# PCB_RFID-Project.net
KiCad netlist of a schematic drawn in Altium Designer
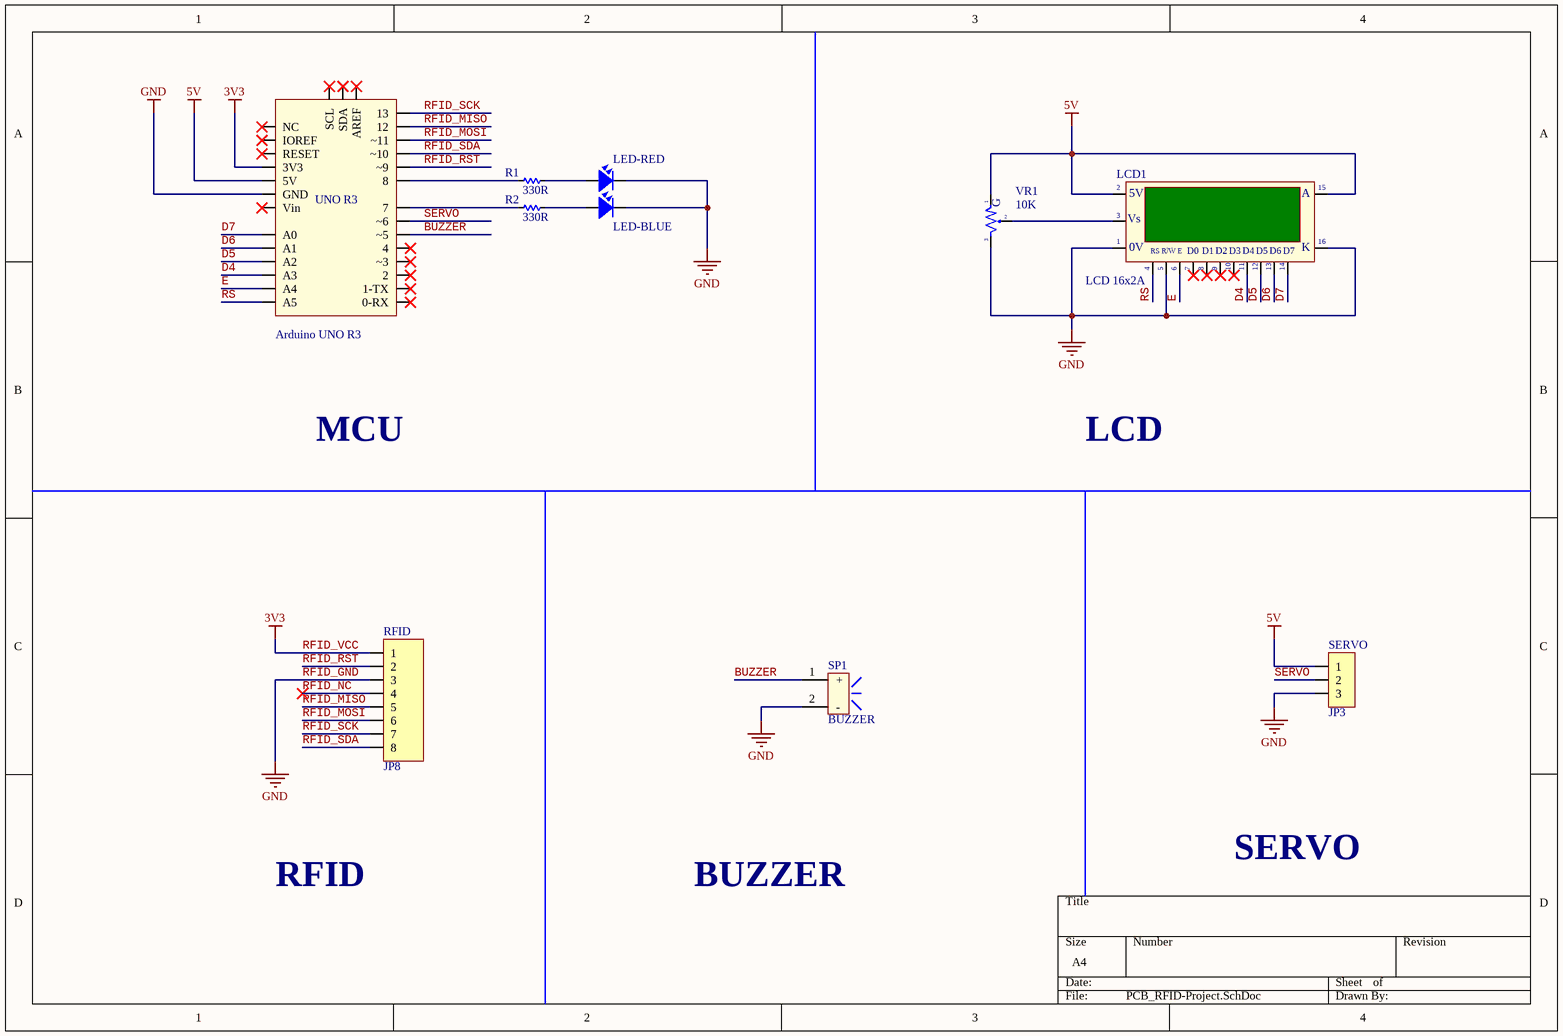
[diagram p0: PCB_RFID-Project.SchDoc]

(export (version "E")
  (design (tool "Eeschema 10.0.6"))
  (components
    (comp (ref "Arduino UNO R3")
      (value "Arduino Uno R3")
      (footprint "Arduino UNO R3")
      (description "Arduino UNO R3")
      (libsource (lib "LIBRARY_MuaLinhKien") (part "Arduino Uno R3"))
    )
    (comp (ref "LCD1")
      (value "LCD 16x2A")
      (footprint "LCD16X2")
      (description "LCD dipslay 16 char, 2 line")
      (libsource (lib "MinhHa_Integrated_Library") (part "LCD16x2A"))
    )
    (comp (ref "LED-BLUE")
      (value "LED")
      (footprint "LED-5MM-BLUE")
      (description "LED Single colour Green and Red")
      (libsource (lib "LIBRARY_MuaLinhKien") (part "LED"))
    )
    (comp (ref "LED-RED")
      (value "LED")
      (footprint "LED-5MM-RED")
      (description "LED Single colour Green and Red")
      (libsource (lib "LIBRARY_MuaLinhKien") (part "LED"))
    )
    (comp (ref "R1")
      (value "330R")
      (footprint "RES-1/4W")
      (description "Res")
      (fields
        (field (name "MANUFACTURER") "Generic Components")
        (field (name "PUBLISHER") "Altium Hobart Technology Centre")
      )
      (libsource (lib "LIBRARY_MuaLinhKien") (part "Res"))
    )
    (comp (ref "R2")
      (value "330R")
      (footprint "RES-1/4W")
      (description "Res")
      (fields
        (field (name "MANUFACTURER") "Generic Components")
        (field (name "PUBLISHER") "Altium Hobart Technology Centre")
      )
      (libsource (lib "LIBRARY_MuaLinhKien") (part "Res"))
    )
    (comp (ref "RFID")
      (value "JP8")
      (footprint "JP8-D1T")
      (description "WR-PHD 2.54 mm Angled Socket Header")
      (fields
        (field (name "MANUFACTURER") "Würth Elektronik eiSos GmbH")
        (field (name "PARTNO") "613008143121")
        (field (name "CREATED BY") "Karrer Zheng")
      )
      (libsource (lib "LIBRARY_MuaLinhKien") (part "JP8"))
    )
    (comp (ref "SERVO")
      (value "JP3")
      (footprint "JP3-D1T")
      (description "WR-PHD 2.54 mm Angled Socket Header")
      (fields
        (field (name "MANUFACTURER") "Würth Elektronik eiSos GmbH")
        (field (name "PARTNO") "613003143121")
        (field (name "CREATED BY") "Karrer Zheng")
      )
      (libsource (lib "LIBRARY_MuaLinhKien") (part "JP3"))
    )
    (comp (ref "SP1")
      (value "BUZZER")
      (footprint "Buzzer 5V 9x1.2mm")
      (description "Buzzer through hole (3V3/5V/12V)")
      (libsource (lib "Duc") (part "Speaker"))
    )
    (comp (ref "VR1")
      (value "10K")
      (footprint "VR-S2")
      (description "Var Resistor")
      (libsource (lib "LIBRARY_MuaLinhKien") (part "VR-S"))
    )
  )
  (nets
    (net (code "1") (name "/BUZZER") (class "Default")
      (node (ref "Arduino UNO R3") (pin "~5") (pinfunction "~5_~5") (pintype "passive"))
      (node (ref "SP1") (pin "1") (pinfunction "+_1") (pintype "passive"))
    )
    (net (code "2") (name "/D4") (class "Default")
      (node (ref "Arduino UNO R3") (pin "A3") (pinfunction "A3_A3") (pintype "passive"))
      (node (ref "LCD1") (pin "11") (pinfunction "D4_11") (pintype "passive"))
    )
    (net (code "3") (name "/D5") (class "Default")
      (node (ref "Arduino UNO R3") (pin "A2") (pinfunction "A2_A2") (pintype "passive"))
      (node (ref "LCD1") (pin "12") (pinfunction "D5_12") (pintype "passive"))
    )
    (net (code "4") (name "/D6") (class "Default")
      (node (ref "Arduino UNO R3") (pin "A1") (pinfunction "A1_A1") (pintype "passive"))
      (node (ref "LCD1") (pin "13") (pinfunction "D6_13") (pintype "passive"))
    )
    (net (code "5") (name "/D7") (class "Default")
      (node (ref "Arduino UNO R3") (pin "A0") (pinfunction "A0_A0") (pintype "passive"))
      (node (ref "LCD1") (pin "14") (pinfunction "D7_14") (pintype "passive"))
    )
    (net (code "6") (name "/E") (class "Default")
      (node (ref "Arduino UNO R3") (pin "A4") (pinfunction "A4_A4") (pintype "passive"))
      (node (ref "LCD1") (pin "6") (pinfunction "~{EN}_6") (pintype "passive"))
    )
    (net (code "7") (name "/RFID_MISO") (class "Default")
      (node (ref "Arduino UNO R3") (pin "12") (pinfunction "12_12") (pintype "passive"))
      (node (ref "RFID") (pin "5") (pinfunction "5_5") (pintype "passive"))
    )
    (net (code "8") (name "/RFID_MOSI") (class "Default")
      (node (ref "Arduino UNO R3") (pin "~11") (pinfunction "~11_~11") (pintype "passive"))
      (node (ref "RFID") (pin "6") (pinfunction "6_6") (pintype "passive"))
    )
    (net (code "9") (name "/RFID_NC") (class "Default")
      (node (ref "RFID") (pin "4") (pinfunction "4_4") (pintype "passive+no_connect"))
    )
    (net (code "10") (name "/RFID_RST") (class "Default")
      (node (ref "Arduino UNO R3") (pin "~9") (pinfunction "~9_~9") (pintype "passive"))
      (node (ref "RFID") (pin "2") (pinfunction "2_2") (pintype "passive"))
    )
    (net (code "11") (name "/RFID_SCK") (class "Default")
      (node (ref "Arduino UNO R3") (pin "13") (pinfunction "13_13") (pintype "passive"))
      (node (ref "RFID") (pin "7") (pinfunction "7_7") (pintype "passive"))
    )
    (net (code "12") (name "/RFID_SDA") (class "Default")
      (node (ref "Arduino UNO R3") (pin "~10") (pinfunction "~10_~10") (pintype "passive"))
      (node (ref "RFID") (pin "8") (pinfunction "8_8") (pintype "passive"))
    )
    (net (code "13") (name "/RS") (class "Default")
      (node (ref "Arduino UNO R3") (pin "A5") (pinfunction "A5_A5") (pintype "passive"))
      (node (ref "LCD1") (pin "4") (pinfunction "RS_4") (pintype "passive"))
    )
    (net (code "14") (name "/SERVO") (class "Default")
      (node (ref "Arduino UNO R3") (pin "~6") (pinfunction "~6_~6") (pintype "passive"))
      (node (ref "SERVO") (pin "2") (pinfunction "2_2") (pintype "passive"))
    )
    (net (code "15") (name "3V3") (class "Default")
      (node (ref "Arduino UNO R3") (pin "3V3") (pinfunction "3V3_3V3") (pintype "passive"))
      (node (ref "RFID") (pin "1") (pinfunction "1_1") (pintype "passive"))
    )
    (net (code "16") (name "5V") (class "Default")
      (node (ref "Arduino UNO R3") (pin "5V") (pinfunction "5V_5V") (pintype "passive"))
      (node (ref "LCD1") (pin "15") (pinfunction "A_15") (pintype "passive"))
      (node (ref "LCD1") (pin "2") (pinfunction "VDD_2") (pintype "passive"))
      (node (ref "SERVO") (pin "1") (pinfunction "1_1") (pintype "passive"))
      (node (ref "VR1") (pin "1") (pinfunction "1_1") (pintype "passive"))
    )
    (net (code "17") (name "GND") (class "Default")
      (node (ref "Arduino UNO R3") (pin "GND") (pinfunction "GND_GND") (pintype "passive"))
      (node (ref "LCD1") (pin "1") (pinfunction "GND_1") (pintype "passive"))
      (node (ref "LCD1") (pin "16") (pinfunction "K_16") (pintype "passive"))
      (node (ref "LCD1") (pin "5") (pinfunction "R/~{W}_5") (pintype "passive"))
      (node (ref "LED-BLUE") (pin "2") (pinfunction "2_2") (pintype "passive"))
      (node (ref "LED-RED") (pin "2") (pinfunction "2_2") (pintype "passive"))
      (node (ref "RFID") (pin "3") (pinfunction "3_3") (pintype "passive"))
      (node (ref "SERVO") (pin "3") (pinfunction "3_3") (pintype "passive"))
      (node (ref "SP1") (pin "2") (pinfunction "-_2") (pintype "passive"))
      (node (ref "VR1") (pin "3") (pinfunction "3_3") (pintype "passive"))
    )
    (net (code "18") (name "Net-(Arduino UNO R3-Pad7)") (class "Default")
      (node (ref "Arduino UNO R3") (pin "7") (pinfunction "7_7") (pintype "passive"))
      (node (ref "R2") (pin "2") (pinfunction "2_2") (pintype "passive"))
    )
    (net (code "19") (name "Net-(Arduino UNO R3-Pad8)") (class "Default")
      (node (ref "Arduino UNO R3") (pin "8") (pinfunction "8_8") (pintype "passive"))
      (node (ref "R1") (pin "2") (pinfunction "2_2") (pintype "passive"))
    )
    (net (code "20") (name "Net-(LCD1-VEE)") (class "Default")
      (node (ref "LCD1") (pin "3") (pinfunction "VEE_3") (pintype "passive"))
      (node (ref "VR1") (pin "2") (pinfunction "2_2") (pintype "passive"))
    )
    (net (code "21") (name "Net-(LED-BLUE-Pad1)") (class "Default")
      (node (ref "LED-BLUE") (pin "1") (pinfunction "1_1") (pintype "passive"))
      (node (ref "R2") (pin "1") (pinfunction "1_1") (pintype "passive"))
    )
    (net (code "22") (name "Net-(LED-RED-Pad1)") (class "Default")
      (node (ref "LED-RED") (pin "1") (pinfunction "1_1") (pintype "passive"))
      (node (ref "R1") (pin "1") (pinfunction "1_1") (pintype "passive"))
    )
    (net (code "23") (name "unconnected-(Arduino UNO R3-Pad0-RX)") (class "Default")
      (node (ref "Arduino UNO R3") (pin "0-RX") (pinfunction "0-RX_0-RX") (pintype "passive+no_connect"))
    )
    (net (code "24") (name "unconnected-(Arduino UNO R3-Pad1-TX)") (class "Default")
      (node (ref "Arduino UNO R3") (pin "1-TX") (pinfunction "1-TX_1-TX") (pintype "passive+no_connect"))
    )
    (net (code "25") (name "unconnected-(Arduino UNO R3-Pad2)") (class "Default")
      (node (ref "Arduino UNO R3") (pin "2") (pinfunction "2_2") (pintype "passive+no_connect"))
    )
    (net (code "26") (name "unconnected-(Arduino UNO R3-Pad4)") (class "Default")
      (node (ref "Arduino UNO R3") (pin "4") (pinfunction "4_4") (pintype "passive+no_connect"))
    )
    (net (code "27") (name "unconnected-(Arduino UNO R3-PadAREF)") (class "Default")
      (node (ref "Arduino UNO R3") (pin "AREF") (pinfunction "AREF_AREF") (pintype "passive+no_connect"))
    )
    (net (code "28") (name "unconnected-(Arduino UNO R3-PadIOREF)") (class "Default")
      (node (ref "Arduino UNO R3") (pin "IOREF") (pinfunction "IOREF_IOREF") (pintype "passive+no_connect"))
    )
    (net (code "29") (name "unconnected-(Arduino UNO R3-PadNC)") (class "Default")
      (node (ref "Arduino UNO R3") (pin "NC") (pinfunction "NC_NC") (pintype "passive+no_connect"))
    )
    (net (code "30") (name "unconnected-(Arduino UNO R3-PadRESET)") (class "Default")
      (node (ref "Arduino UNO R3") (pin "RESET") (pinfunction "RESET_RESET") (pintype "passive+no_connect"))
    )
    (net (code "31") (name "unconnected-(Arduino UNO R3-PadSCL)") (class "Default")
      (node (ref "Arduino UNO R3") (pin "SCL") (pinfunction "SCL_SCL") (pintype "passive+no_connect"))
    )
    (net (code "32") (name "unconnected-(Arduino UNO R3-PadSDA)") (class "Default")
      (node (ref "Arduino UNO R3") (pin "SDA") (pinfunction "SDA_SDA") (pintype "passive+no_connect"))
    )
    (net (code "33") (name "unconnected-(Arduino UNO R3-PadVin)") (class "Default")
      (node (ref "Arduino UNO R3") (pin "Vin") (pinfunction "Vin_Vin") (pintype "passive+no_connect"))
    )
    (net (code "34") (name "unconnected-(Arduino UNO R3-Pad~3)") (class "Default")
      (node (ref "Arduino UNO R3") (pin "~3") (pinfunction "~3_~3") (pintype "passive+no_connect"))
    )
    (net (code "35") (name "unconnected-(LCD1-D0-Pad7)") (class "Default")
      (node (ref "LCD1") (pin "7") (pinfunction "D0_7") (pintype "passive+no_connect"))
    )
    (net (code "36") (name "unconnected-(LCD1-D1-Pad8)") (class "Default")
      (node (ref "LCD1") (pin "8") (pinfunction "D1_8") (pintype "passive+no_connect"))
    )
    (net (code "37") (name "unconnected-(LCD1-D2-Pad9)") (class "Default")
      (node (ref "LCD1") (pin "9") (pinfunction "D2_9") (pintype "passive+no_connect"))
    )
    (net (code "38") (name "unconnected-(LCD1-D3-Pad10)") (class "Default")
      (node (ref "LCD1") (pin "10") (pinfunction "D3_10") (pintype "passive+no_connect"))
    )
  )
)
